# powerrgulation.net
KiCad netlist of a schematic drawn in EAGLE
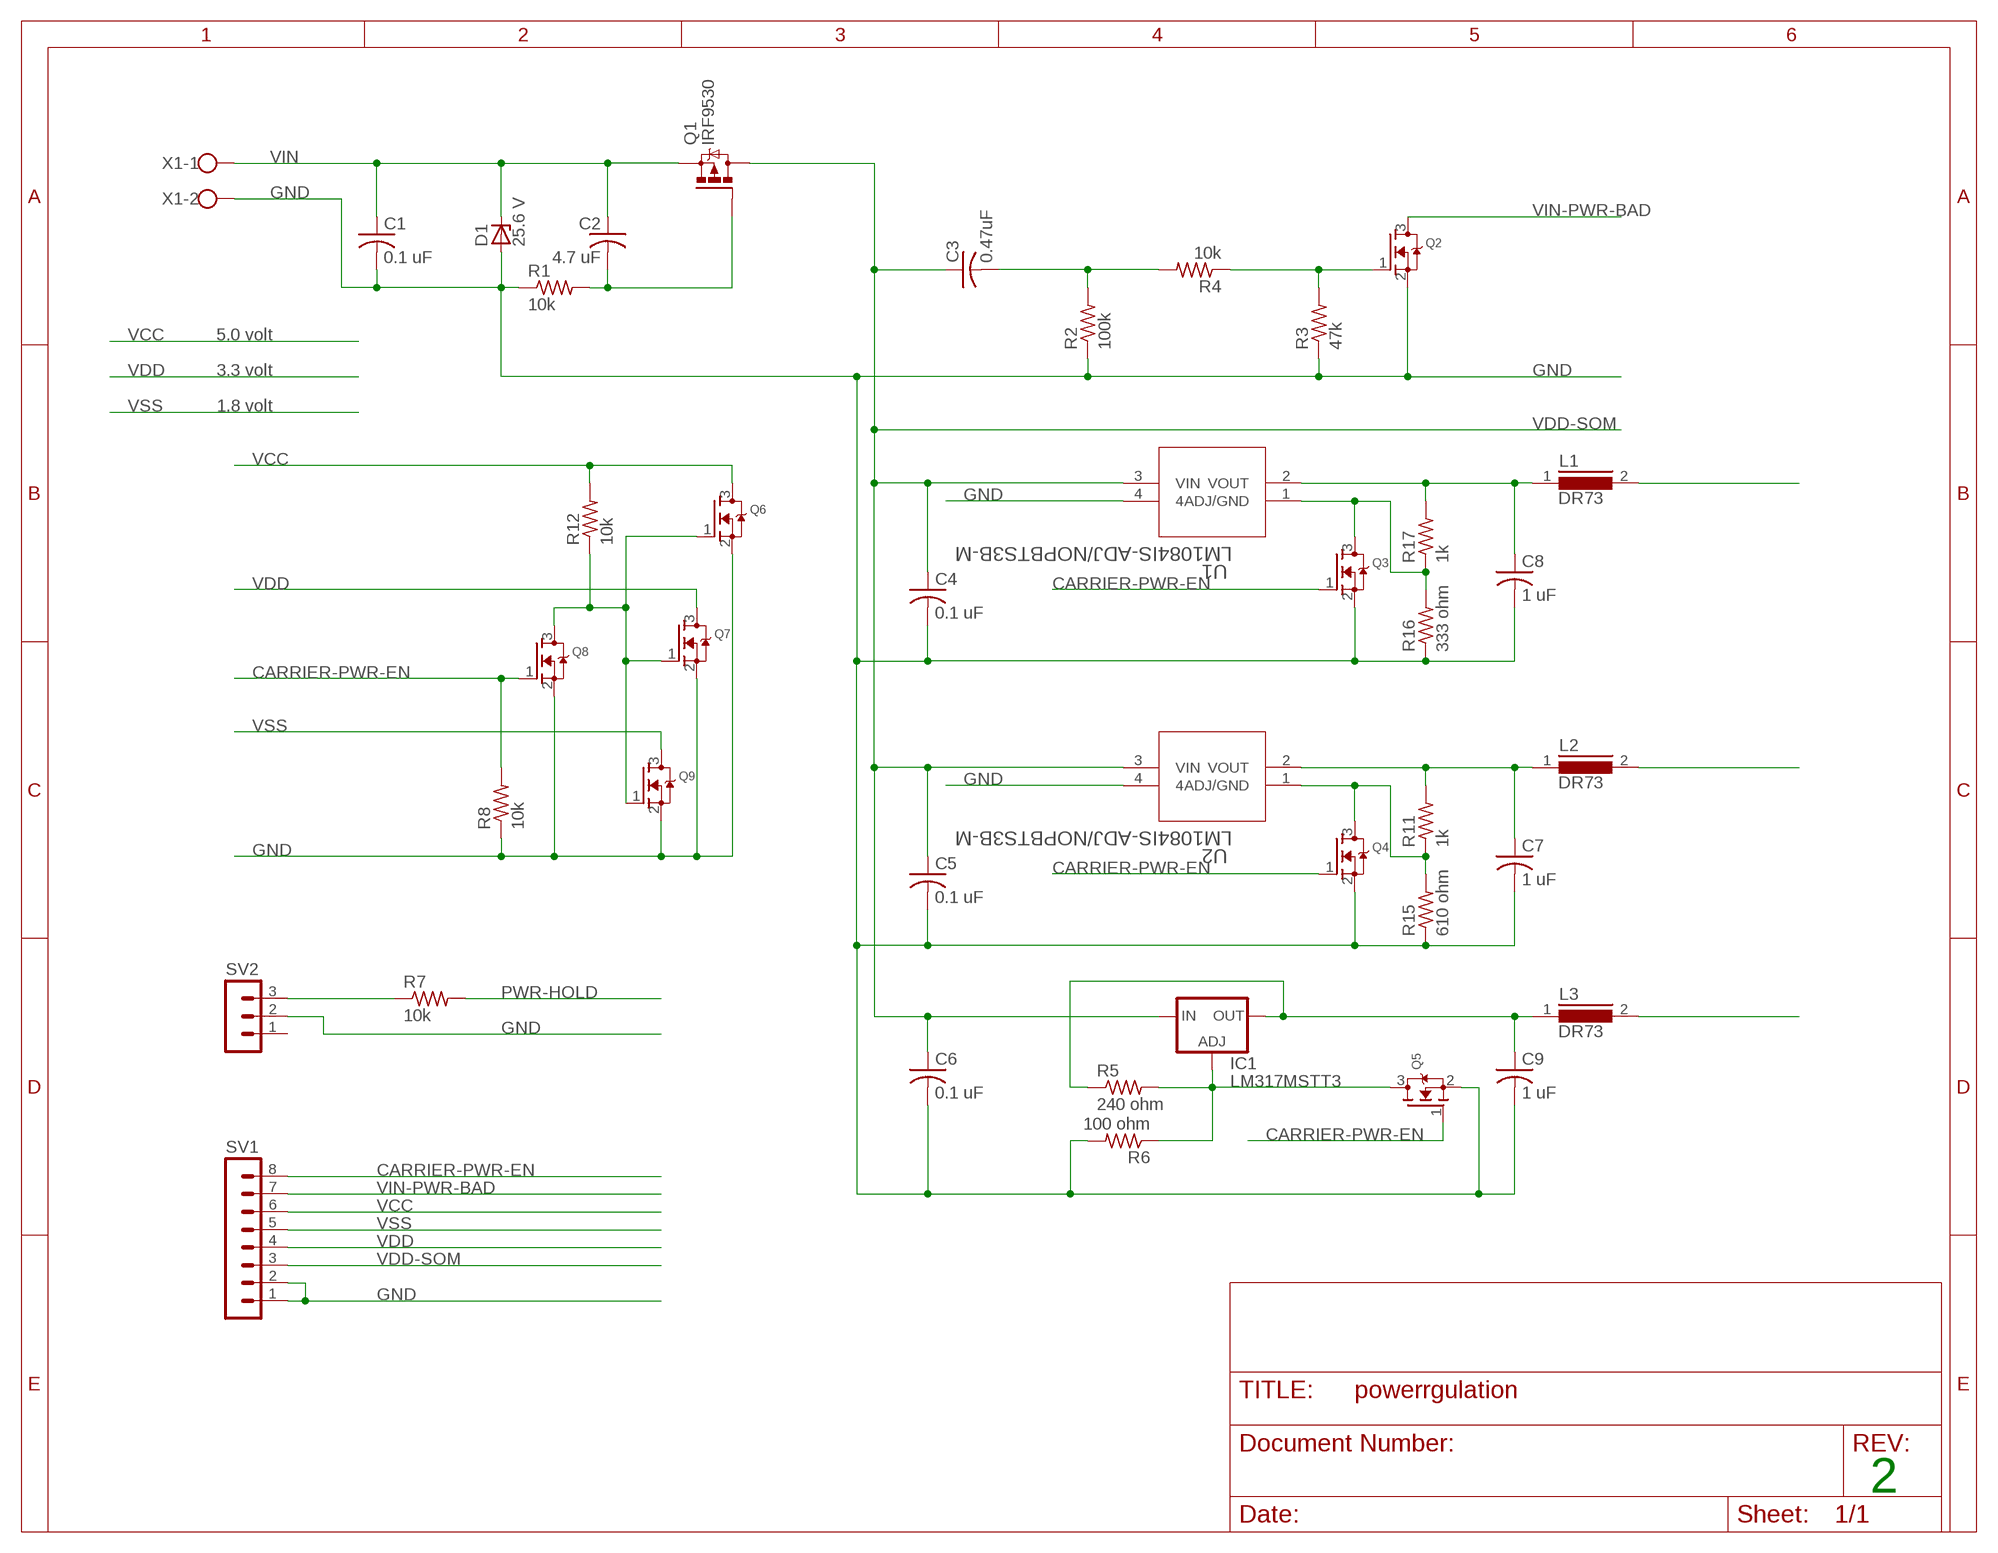
[diagram p0: schematic, sheet 1]

(export (version "E")
  (design (tool "Eeschema 10.0.6"))
  (components
    (comp (ref "C1")
      (value "0.1 uF")
      (footprint "eagle-import:C0805")
      (libsource (lib "eagle-import") (part "resistor_348_C-USC0805"))
    )
    (comp (ref "C2")
      (value "4.7 uF")
      (footprint "eagle-import:C0805")
      (libsource (lib "eagle-import") (part "resistor_348_C-USC0805"))
    )
    (comp (ref "C3")
      (value "0.47uF")
      (footprint "eagle-import:C0805")
      (libsource (lib "eagle-import") (part "C-USC0805"))
    )
    (comp (ref "C4")
      (value "0.1 uF")
      (footprint "eagle-import:C0805")
      (libsource (lib "eagle-import") (part "rcl_334_C-USC0805"))
    )
    (comp (ref "C5")
      (value "0.1 uF")
      (footprint "eagle-import:C0805")
      (libsource (lib "eagle-import") (part "rcl_334_C-USC0805"))
    )
    (comp (ref "C6")
      (value "0.1 uF")
      (footprint "eagle-import:C0805")
      (libsource (lib "eagle-import") (part "rcl_334_C-USC0805"))
    )
    (comp (ref "C7")
      (value "1 uF")
      (footprint "eagle-import:C0805")
      (libsource (lib "eagle-import") (part "rcl_334_C-USC0805"))
    )
    (comp (ref "C8")
      (value "1 uF")
      (footprint "eagle-import:C0805")
      (libsource (lib "eagle-import") (part "rcl_334_C-USC0805"))
    )
    (comp (ref "C9")
      (value "1 uF")
      (footprint "eagle-import:C0805")
      (libsource (lib "eagle-import") (part "rcl_334_C-USC0805"))
    )
    (comp (ref "D1")
      (value "25.6 V")
      (footprint "eagle-import:SOT23")
      (libsource (lib "eagle-import") (part "ZENER-DIODESOT23"))
    )
    (comp (ref "IC1")
      (value "LM317MSTT3")
      (footprint "eagle-import:SOT223")
      (libsource (lib "eagle-import") (part "LM317?MSTT3"))
    )
    (comp (ref "L1")
      (value "DR73")
      (footprint "eagle-import:DR73")
      (libsource (lib "eagle-import") (part "DR73"))
    )
    (comp (ref "L2")
      (value "DR73")
      (footprint "eagle-import:DR73")
      (libsource (lib "eagle-import") (part "DR73"))
    )
    (comp (ref "L3")
      (value "DR73")
      (footprint "eagle-import:DR73")
      (libsource (lib "eagle-import") (part "DR73"))
    )
    (comp (ref "Q1")
      (value "IRF9530")
      (footprint "eagle-import:TO220BV")
      (libsource (lib "eagle-import") (part "IRF9530"))
    )
    (comp (ref "Q2")
      (value "MOSFET-NREFLOW")
      (footprint "eagle-import:SOT23")
      (libsource (lib "eagle-import") (part "MOSFET-NREFLOW"))
    )
    (comp (ref "Q3")
      (value "MOSFET-NREFLOW")
      (footprint "eagle-import:SOT23")
      (libsource (lib "eagle-import") (part "MOSFET-NREFLOW"))
    )
    (comp (ref "Q4")
      (value "MOSFET-NREFLOW")
      (footprint "eagle-import:SOT23")
      (libsource (lib "eagle-import") (part "MOSFET-NREFLOW"))
    )
    (comp (ref "Q5")
      (value "MOSFET-NREFLOW")
      (footprint "eagle-import:SOT23")
      (libsource (lib "eagle-import") (part "MOSFET-NREFLOW"))
    )
    (comp (ref "Q6")
      (value "MOSFET-NREFLOW")
      (footprint "eagle-import:SOT23")
      (libsource (lib "eagle-import") (part "MOSFET-NREFLOW"))
    )
    (comp (ref "Q7")
      (value "MOSFET-NREFLOW")
      (footprint "eagle-import:SOT23")
      (libsource (lib "eagle-import") (part "MOSFET-NREFLOW"))
    )
    (comp (ref "Q8")
      (value "MOSFET-NREFLOW")
      (footprint "eagle-import:SOT23")
      (libsource (lib "eagle-import") (part "MOSFET-NREFLOW"))
    )
    (comp (ref "Q9")
      (value "MOSFET-NREFLOW")
      (footprint "eagle-import:SOT23")
      (libsource (lib "eagle-import") (part "MOSFET-NREFLOW"))
    )
    (comp (ref "R1")
      (value "10k")
      (footprint "eagle-import:R0603")
      (libsource (lib "eagle-import") (part "rcl_334_R-US_R0603"))
    )
    (comp (ref "R2")
      (value "100k")
      (footprint "eagle-import:R0603")
      (libsource (lib "eagle-import") (part "R-US_R0603"))
    )
    (comp (ref "R3")
      (value "47k")
      (footprint "eagle-import:R0603")
      (libsource (lib "eagle-import") (part "R-US_R0603"))
    )
    (comp (ref "R4")
      (value "10k")
      (footprint "eagle-import:R0603")
      (libsource (lib "eagle-import") (part "R-US_R0603"))
    )
    (comp (ref "R5")
      (value "240 ohm")
      (footprint "eagle-import:R0603")
      (libsource (lib "eagle-import") (part "rcl_334_R-US_R0603"))
    )
    (comp (ref "R6")
      (value "100 ohm")
      (footprint "eagle-import:R0603")
      (libsource (lib "eagle-import") (part "rcl_334_R-US_R0603"))
    )
    (comp (ref "R7")
      (value "10k")
      (footprint "eagle-import:R0603")
      (libsource (lib "eagle-import") (part "rcl_334_R-US_R0603"))
    )
    (comp (ref "R8")
      (value "10k")
      (footprint "eagle-import:R0603")
      (libsource (lib "eagle-import") (part "resistor_348_R-US_R0603"))
    )
    (comp (ref "R11")
      (value "1k")
      (footprint "eagle-import:R0603")
      (libsource (lib "eagle-import") (part "resistor_348_R-US_R0603"))
    )
    (comp (ref "R12")
      (value "10k")
      (footprint "eagle-import:R0603")
      (libsource (lib "eagle-import") (part "resistor_348_R-US_R0603"))
    )
    (comp (ref "R15")
      (value "610 ohm")
      (footprint "eagle-import:R0603")
      (libsource (lib "eagle-import") (part "resistor_348_R-US_R0603"))
    )
    (comp (ref "R16")
      (value "333 ohm")
      (footprint "eagle-import:R0603")
      (libsource (lib "eagle-import") (part "resistor_348_R-US_R0603"))
    )
    (comp (ref "R17")
      (value "1k")
      (footprint "eagle-import:R0603")
      (libsource (lib "eagle-import") (part "resistor_348_R-US_R0603"))
    )
    (comp (ref "SV1")
      (value "MA08-1")
      (footprint "eagle-import:MA08-1")
      (libsource (lib "eagle-import") (part "MA08-1"))
    )
    (comp (ref "SV2")
      (value "MA03-1")
      (footprint "eagle-import:MA03-1")
      (libsource (lib "eagle-import") (part "MA03-1"))
    )
    (comp (ref "U1")
      (value "LM1084IS-ADJ/NOPBTS3B-M")
      (footprint "eagle-import:TS3B-M")
      (fields (field (name "MANUFACTURER_PART_NUMBER") "LM1084ISADJNOPB"))
      (libsource (lib "eagle-import") (part "LM1084IS-ADJ/NOPBTS3B-M"))
    )
    (comp (ref "U2")
      (value "LM1084IS-ADJ/NOPBTS3B-M")
      (footprint "eagle-import:TS3B-M")
      (fields (field (name "MANUFACTURER_PART_NUMBER") "LM1084ISADJNOPB"))
      (libsource (lib "eagle-import") (part "LM1084IS-ADJ/NOPBTS3B-M"))
    )
    (comp (ref "X1")
      (value "W237-102")
      (footprint "eagle-import:W237-102")
      (fields (field (name "MPN") "237-102"))
      (libsource (lib "eagle-import") (part "W237-102"))
    )
  )
  (nets
    (net (code "1") (name "/CARRIER-PWR-EN") (class "Default")
      (node (ref "Q3") (pin "1") (pinfunction "G_1") (pintype "bidirectional"))
      (node (ref "Q4") (pin "1") (pinfunction "G_1") (pintype "bidirectional"))
      (node (ref "Q5") (pin "1") (pinfunction "G_1") (pintype "bidirectional"))
      (node (ref "Q8") (pin "1") (pinfunction "G_1") (pintype "bidirectional"))
      (node (ref "R8") (pin "2") (pinfunction "2_2") (pintype "passive"))
      (node (ref "SV1") (pin "8") (pinfunction "8_8") (pintype "passive"))
    )
    (net (code "2") (name "/GND") (class "Default")
      (node (ref "C1") (pin "2") (pinfunction "2_2") (pintype "passive"))
      (node (ref "C4") (pin "2") (pinfunction "2_2") (pintype "passive"))
      (node (ref "C5") (pin "2") (pinfunction "2_2") (pintype "passive"))
      (node (ref "C6") (pin "2") (pinfunction "2_2") (pintype "passive"))
      (node (ref "C7") (pin "2") (pinfunction "2_2") (pintype "passive"))
      (node (ref "C8") (pin "2") (pinfunction "2_2") (pintype "passive"))
      (node (ref "C9") (pin "2") (pinfunction "2_2") (pintype "passive"))
      (node (ref "D1") (pin "1") (pinfunction "A_1") (pintype "passive"))
      (node (ref "Q2") (pin "2") (pinfunction "S_2") (pintype "bidirectional"))
      (node (ref "Q3") (pin "2") (pinfunction "S_2") (pintype "bidirectional"))
      (node (ref "Q4") (pin "2") (pinfunction "S_2") (pintype "bidirectional"))
      (node (ref "Q5") (pin "2") (pinfunction "S_2") (pintype "bidirectional"))
      (node (ref "Q6") (pin "2") (pinfunction "S_2") (pintype "bidirectional"))
      (node (ref "Q7") (pin "2") (pinfunction "S_2") (pintype "bidirectional"))
      (node (ref "Q8") (pin "2") (pinfunction "S_2") (pintype "bidirectional"))
      (node (ref "Q9") (pin "2") (pinfunction "S_2") (pintype "bidirectional"))
      (node (ref "R1") (pin "1") (pinfunction "1_1") (pintype "passive"))
      (node (ref "R15") (pin "1") (pinfunction "1_1") (pintype "passive"))
      (node (ref "R16") (pin "1") (pinfunction "1_1") (pintype "passive"))
      (node (ref "R2") (pin "1") (pinfunction "1_1") (pintype "passive"))
      (node (ref "R3") (pin "1") (pinfunction "1_1") (pintype "passive"))
      (node (ref "R6") (pin "2") (pinfunction "2_2") (pintype "passive"))
      (node (ref "R8") (pin "1") (pinfunction "1_1") (pintype "passive"))
      (node (ref "SV1") (pin "1") (pinfunction "1_1") (pintype "passive"))
      (node (ref "SV1") (pin "2") (pinfunction "2_2") (pintype "passive"))
      (node (ref "SV2") (pin "2") (pinfunction "2_2") (pintype "passive"))
      (node (ref "U1") (pin "4") (pinfunction "4_4") (pintype "passive"))
      (node (ref "U2") (pin "4") (pinfunction "4_4") (pintype "passive"))
      (node (ref "X1") (pin "2") (pinfunction "KL_2") (pintype "passive"))
    )
    (net (code "3") (name "/PWR-HOLD") (class "Default")
      (node (ref "C2") (pin "2") (pinfunction "2_2") (pintype "passive"))
      (node (ref "Q1") (pin "G") (pinfunction "G_G") (pintype "passive"))
      (node (ref "R1") (pin "2") (pinfunction "2_2") (pintype "passive"))
      (node (ref "R7") (pin "2") (pinfunction "2_2") (pintype "passive"))
    )
    (net (code "4") (name "/VCC") (class "Default")
      (node (ref "L1") (pin "2") (pinfunction "2_2") (pintype "passive"))
      (node (ref "Q6") (pin "3") (pinfunction "D_3") (pintype "bidirectional"))
      (node (ref "R12") (pin "2") (pinfunction "2_2") (pintype "passive"))
      (node (ref "SV1") (pin "6") (pinfunction "6_6") (pintype "passive"))
    )
    (net (code "5") (name "/VDD") (class "Default")
      (node (ref "L2") (pin "2") (pinfunction "2_2") (pintype "passive"))
      (node (ref "Q7") (pin "3") (pinfunction "D_3") (pintype "bidirectional"))
      (node (ref "SV1") (pin "4") (pinfunction "4_4") (pintype "passive"))
    )
    (net (code "6") (name "/VDD-SOM") (class "Default")
      (node (ref "C3") (pin "1") (pinfunction "1_1") (pintype "passive"))
      (node (ref "C4") (pin "1") (pinfunction "1_1") (pintype "passive"))
      (node (ref "C5") (pin "1") (pinfunction "1_1") (pintype "passive"))
      (node (ref "C6") (pin "1") (pinfunction "1_1") (pintype "passive"))
      (node (ref "IC1") (pin "3") (pinfunction "IN_3") (pintype "input"))
      (node (ref "Q1") (pin "D") (pinfunction "D_D") (pintype "passive"))
      (node (ref "SV1") (pin "3") (pinfunction "3_3") (pintype "passive"))
      (node (ref "U1") (pin "3") (pinfunction "VIN_3") (pintype "input"))
      (node (ref "U2") (pin "3") (pinfunction "VIN_3") (pintype "input"))
    )
    (net (code "7") (name "/VIN") (class "Default")
      (node (ref "C1") (pin "1") (pinfunction "1_1") (pintype "passive"))
      (node (ref "C2") (pin "1") (pinfunction "1_1") (pintype "passive"))
      (node (ref "D1") (pin "3") (pinfunction "C_3") (pintype "passive"))
      (node (ref "Q1") (pin "S") (pinfunction "S_S") (pintype "passive"))
      (node (ref "X1") (pin "1") (pinfunction "KL_1") (pintype "passive"))
    )
    (net (code "8") (name "/VIN-PWR-BAD") (class "Default")
      (node (ref "Q2") (pin "3") (pinfunction "D_3") (pintype "bidirectional"))
      (node (ref "SV1") (pin "7") (pinfunction "7_7") (pintype "passive"))
    )
    (net (code "9") (name "/VSS") (class "Default")
      (node (ref "L3") (pin "2") (pinfunction "2_2") (pintype "passive"))
      (node (ref "Q9") (pin "3") (pinfunction "D_3") (pintype "bidirectional"))
      (node (ref "SV1") (pin "5") (pinfunction "5_5") (pintype "passive"))
    )
    (net (code "10") (name "Net-(C3-Pad2)") (class "Default")
      (node (ref "C3") (pin "2") (pinfunction "2_2") (pintype "passive"))
      (node (ref "R2") (pin "2") (pinfunction "2_2") (pintype "passive"))
      (node (ref "R4") (pin "2") (pinfunction "2_2") (pintype "passive"))
    )
    (net (code "11") (name "Net-(IC1-ADJ)") (class "Default")
      (node (ref "IC1") (pin "1") (pinfunction "ADJ_1") (pintype "input"))
      (node (ref "Q5") (pin "3") (pinfunction "D_3") (pintype "bidirectional"))
      (node (ref "R5") (pin "2") (pinfunction "2_2") (pintype "passive"))
      (node (ref "R6") (pin "1") (pinfunction "1_1") (pintype "passive"))
    )
    (net (code "12") (name "Net-(IC1-OUT)") (class "Default")
      (node (ref "C9") (pin "1") (pinfunction "1_1") (pintype "passive"))
      (node (ref "IC1") (pin "4") (pinfunction "OUT_4") (pintype "passive"))
      (node (ref "L3") (pin "1") (pinfunction "1_1") (pintype "passive"))
      (node (ref "R5") (pin "1") (pinfunction "1_1") (pintype "passive"))
    )
    (net (code "13") (name "Net-(Q2-G)") (class "Default")
      (node (ref "Q2") (pin "1") (pinfunction "G_1") (pintype "bidirectional"))
      (node (ref "R3") (pin "2") (pinfunction "2_2") (pintype "passive"))
      (node (ref "R4") (pin "1") (pinfunction "1_1") (pintype "passive"))
    )
    (net (code "14") (name "Net-(Q3-D)") (class "Default")
      (node (ref "Q3") (pin "3") (pinfunction "D_3") (pintype "bidirectional"))
      (node (ref "R16") (pin "2") (pinfunction "2_2") (pintype "passive"))
      (node (ref "R17") (pin "1") (pinfunction "1_1") (pintype "passive"))
      (node (ref "U1") (pin "1") (pinfunction "ADJ/GND_1") (pintype "passive"))
    )
    (net (code "15") (name "Net-(Q4-D)") (class "Default")
      (node (ref "Q4") (pin "3") (pinfunction "D_3") (pintype "bidirectional"))
      (node (ref "R11") (pin "1") (pinfunction "1_1") (pintype "passive"))
      (node (ref "R15") (pin "2") (pinfunction "2_2") (pintype "passive"))
      (node (ref "U2") (pin "1") (pinfunction "ADJ/GND_1") (pintype "passive"))
    )
    (net (code "16") (name "Net-(Q6-G)") (class "Default")
      (node (ref "Q6") (pin "1") (pinfunction "G_1") (pintype "bidirectional"))
      (node (ref "Q7") (pin "1") (pinfunction "G_1") (pintype "bidirectional"))
      (node (ref "Q8") (pin "3") (pinfunction "D_3") (pintype "bidirectional"))
      (node (ref "Q9") (pin "1") (pinfunction "G_1") (pintype "bidirectional"))
      (node (ref "R12") (pin "1") (pinfunction "1_1") (pintype "passive"))
    )
    (net (code "17") (name "Net-(R7-Pad1)") (class "Default")
      (node (ref "R7") (pin "1") (pinfunction "1_1") (pintype "passive"))
      (node (ref "SV2") (pin "3") (pinfunction "3_3") (pintype "passive"))
    )
    (net (code "18") (name "Net-(U1-VOUT)") (class "Default")
      (node (ref "C8") (pin "1") (pinfunction "1_1") (pintype "passive"))
      (node (ref "L1") (pin "1") (pinfunction "1_1") (pintype "passive"))
      (node (ref "R17") (pin "2") (pinfunction "2_2") (pintype "passive"))
      (node (ref "U1") (pin "2") (pinfunction "VOUT_2") (pintype "output"))
    )
    (net (code "19") (name "Net-(U2-VOUT)") (class "Default")
      (node (ref "C7") (pin "1") (pinfunction "1_1") (pintype "passive"))
      (node (ref "L2") (pin "1") (pinfunction "1_1") (pintype "passive"))
      (node (ref "R11") (pin "2") (pinfunction "2_2") (pintype "passive"))
      (node (ref "U2") (pin "2") (pinfunction "VOUT_2") (pintype "output"))
    )
    (net (code "20") (name "unconnected-(SV2-Pad1)") (class "Default")
      (node (ref "SV2") (pin "1") (pinfunction "1_1") (pintype "passive"))
    )
  )
)
